# HIP4082driver.net
KiCad netlist of a schematic drawn in Altium Designer
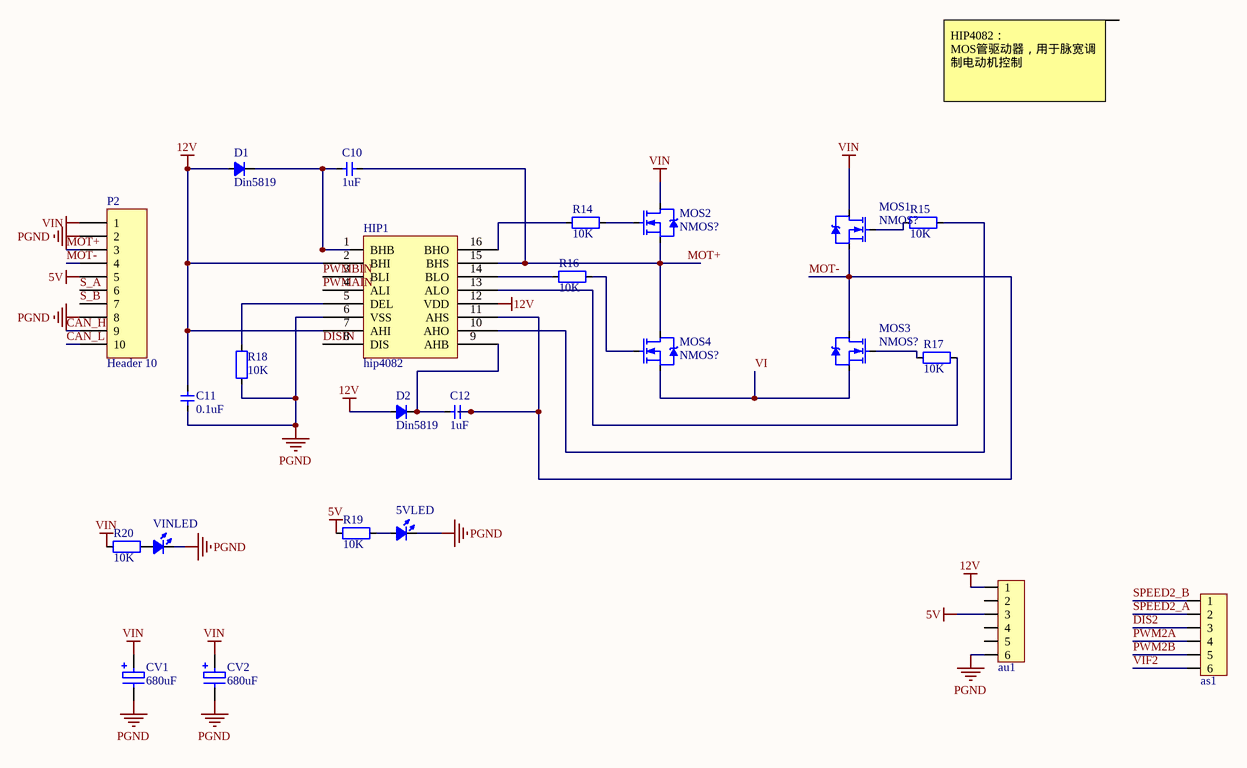
[diagram p0: HIP4082driver.SchDoc]

(export (version "E")
  (design (tool "Eeschema 10.0.6"))
  (components
    (comp (ref "5VLED")
      (value "LED_0805")
      (footprint "LED_0805_BLUE")
      (description "LED")
      (libsource (lib "SCH_Active") (part "LED_0603"))
    )
    (comp (ref "as1")
      (value "HDR1x6_2.54")
      (footprint "HDR1X6_2.54_180")
      (description "Header")
      (libsource (lib "Integrated_Library") (part "HDR1x6_2.54"))
    )
    (comp (ref "au1")
      (value "HDR1x6_2.54")
      (footprint "HDR1X6_2.54_180")
      (description "Header")
      (libsource (lib "Integrated_Library") (part "HDR1x6_2.54"))
    )
    (comp (ref "C10")
      (value "1uF")
      (footprint "CAP_0603")
      (description "Capacitor")
      (fields (field (name "Comment") "Cap_0603"))
      (libsource (lib "Integrated_Library") (part "Cap_0603"))
    )
    (comp (ref "C11")
      (value "0.1uF")
      (footprint "CAP_0603")
      (description "Capacitor")
      (fields (field (name "Comment") "Cap_0603"))
      (libsource (lib "Integrated_Library") (part "Cap_0603"))
    )
    (comp (ref "C12")
      (value "1uF")
      (footprint "CAP_0603")
      (description "Capacitor")
      (fields (field (name "Comment") "Cap_0603"))
      (libsource (lib "Integrated_Library") (part "Cap_0603"))
    )
    (comp (ref "CV1")
      (value "680uF")
      (footprint "CAP_ELE_680UF0.7X5MM")
      (description "电解电容")
      (fields (field (name "PUBLISHER") "Altium Limited"))
      (libsource (lib "Libraries_2014_0618") (part "CAP-ELE"))
    )
    (comp (ref "CV2")
      (value "680uF")
      (footprint "CAP_ELE_680UF0.7X5MM")
      (description "电解电容")
      (fields (field (name "PUBLISHER") "Altium Limited"))
      (libsource (lib "Libraries_2014_0618") (part "CAP-ELE"))
    )
    (comp (ref "D1")
      (value "Din5819")
      (footprint "SOD-323")
      (description "Diode")
      (libsource (lib "Integrated_Library") (part "Diode"))
    )
    (comp (ref "D2")
      (value "Din5819")
      (footprint "SOD-323")
      (description "Diode")
      (libsource (lib "Integrated_Library") (part "Diode"))
    )
    (comp (ref "HIP1") (value "hip4082") (footprint "SOP_E150_16") (libsource (lib "元件库") (part "hip4082")))
    (comp (ref "MOS1")
      (value "NMOS?")
      (footprint "PCB_IntegratedCircuit:TO-252AA")
      (description "MOSFET")
      (fields (field (name "Comment") "MOSFET_N"))
      (libsource (lib "SCH_Active") (part "MOSFET_N"))
    )
    (comp (ref "MOS2")
      (value "NMOS?")
      (footprint "PCB_IntegratedCircuit:TO-252AA")
      (description "MOSFET")
      (fields (field (name "Comment") "MOSFET_N"))
      (libsource (lib "SCH_Active") (part "MOSFET_N"))
    )
    (comp (ref "MOS3")
      (value "NMOS?")
      (footprint "PCB_IntegratedCircuit:TO-252AA")
      (description "MOSFET")
      (fields (field (name "Comment") "MOSFET_N"))
      (libsource (lib "SCH_Active") (part "MOSFET_N"))
    )
    (comp (ref "MOS4")
      (value "NMOS?")
      (footprint "PCB_IntegratedCircuit:TO-252AA")
      (description "MOSFET")
      (fields (field (name "Comment") "MOSFET_N"))
      (libsource (lib "SCH_Active") (part "MOSFET_N"))
    )
    (comp (ref "P2")
      (value "Header 10")
      (footprint "Green_10P")
      (description "Header, 10-Pin")
      (fields (field (name "PUBLISHER") "Altium Limited"))
      (libsource (lib "Libraries_2014_0618") (part "Header 10"))
    )
    (comp (ref "R14")
      (value "10K")
      (footprint "RES_0603")
      (description "Resistor")
      (fields (field (name "Comment") "Res_0603"))
      (libsource (lib "") (part "Res_0603_1"))
    )
    (comp (ref "R15")
      (value "10K")
      (footprint "RES_0603")
      (description "Resistor")
      (fields (field (name "Comment") "Res_0603"))
      (libsource (lib "") (part "Res_0603_1"))
    )
    (comp (ref "R16")
      (value "10K")
      (footprint "RES_0603")
      (description "Resistor")
      (fields (field (name "Comment") "Res_0603"))
      (libsource (lib "") (part "Res_0603_1"))
    )
    (comp (ref "R17")
      (value "10K")
      (footprint "RES_0603")
      (description "Resistor")
      (fields (field (name "Comment") "Res_0603"))
      (libsource (lib "") (part "Res_0603_1"))
    )
    (comp (ref "R18")
      (value "10K")
      (footprint "RES_0603")
      (description "Resistor")
      (fields (field (name "Comment") "Res_0603"))
      (libsource (lib "Integrated_Library") (part "Res_0603"))
    )
    (comp (ref "R19")
      (value "10K")
      (footprint "RES_0603")
      (description "Resistor")
      (fields (field (name "Comment") "Res_0603"))
      (libsource (lib "") (part "Res_0603_1"))
    )
    (comp (ref "R20")
      (value "10K")
      (footprint "RES_0603")
      (description "Resistor")
      (fields (field (name "Comment") "Res_0603"))
      (libsource (lib "") (part "Res_0603_1"))
    )
    (comp (ref "VINLED")
      (value "LED_0805")
      (footprint "LED_0805_RED")
      (description "LED")
      (libsource (lib "SCH_Active") (part "LED_0603"))
    )
  )
  (nets
    (net (code "1") (name "/CAN_H") (class "Default")
      (node (ref "P2") (pin "9") (pinfunction "9_9") (pintype "passive"))
    )
    (net (code "2") (name "/CAN_L") (class "Default")
      (node (ref "P2") (pin "10") (pinfunction "10_10") (pintype "passive"))
    )
    (net (code "3") (name "/DIS2") (class "Default")
      (node (ref "as1") (pin "3") (pinfunction "3_3") (pintype "passive"))
    )
    (net (code "4") (name "/DISIN") (class "Default")
      (node (ref "HIP1") (pin "8") (pinfunction "DIS_8") (pintype "passive"))
    )
    (net (code "5") (name "/MOT+") (class "Default")
      (node (ref "C10") (pin "2") (pinfunction "2_2") (pintype "passive"))
      (node (ref "HIP1") (pin "15") (pinfunction "BHS_15") (pintype "passive"))
      (node (ref "MOS2") (pin "3") (pinfunction "S_3") (pintype "passive"))
      (node (ref "MOS4") (pin "4") (pinfunction "D_4") (pintype "passive"))
      (node (ref "P2") (pin "3") (pinfunction "3_3") (pintype "passive"))
    )
    (net (code "6") (name "/MOT-") (class "Default")
      (node (ref "C12") (pin "2") (pinfunction "2_2") (pintype "passive"))
      (node (ref "HIP1") (pin "11") (pinfunction "AHS_11") (pintype "passive"))
      (node (ref "MOS1") (pin "3") (pinfunction "S_3") (pintype "passive"))
      (node (ref "MOS3") (pin "4") (pinfunction "D_4") (pintype "passive"))
      (node (ref "P2") (pin "4") (pinfunction "4_4") (pintype "passive"))
    )
    (net (code "7") (name "/PWM2A") (class "Default")
      (node (ref "as1") (pin "4") (pinfunction "4_4") (pintype "passive"))
    )
    (net (code "8") (name "/PWM2B") (class "Default")
      (node (ref "as1") (pin "5") (pinfunction "5_5") (pintype "passive"))
    )
    (net (code "9") (name "/PWMAIN") (class "Default")
      (node (ref "HIP1") (pin "4") (pinfunction "ALI_4") (pintype "passive"))
    )
    (net (code "10") (name "/PWMBIN") (class "Default")
      (node (ref "HIP1") (pin "3") (pinfunction "BLI_3") (pintype "passive"))
    )
    (net (code "11") (name "/SPEED2_A") (class "Default")
      (node (ref "as1") (pin "2") (pinfunction "2_2") (pintype "passive"))
    )
    (net (code "12") (name "/SPEED2_B") (class "Default")
      (node (ref "as1") (pin "1") (pinfunction "1_1") (pintype "passive"))
    )
    (net (code "13") (name "/S_A") (class "Default")
      (node (ref "P2") (pin "6") (pinfunction "6_6") (pintype "passive"))
    )
    (net (code "14") (name "/S_B") (class "Default")
      (node (ref "P2") (pin "7") (pinfunction "7_7") (pintype "passive"))
    )
    (net (code "15") (name "/VI") (class "Default")
      (node (ref "MOS3") (pin "3") (pinfunction "S_3") (pintype "passive"))
      (node (ref "MOS4") (pin "3") (pinfunction "S_3") (pintype "passive"))
    )
    (net (code "16") (name "/VIF2") (class "Default")
      (node (ref "as1") (pin "6") (pinfunction "6_6") (pintype "passive"))
    )
    (net (code "17") (name "5V") (class "Default")
      (node (ref "P2") (pin "5") (pinfunction "5_5") (pintype "passive"))
      (node (ref "R19") (pin "1") (pinfunction "1_1") (pintype "passive"))
      (node (ref "au1") (pin "3") (pinfunction "3_3") (pintype "passive"))
    )
    (net (code "18") (name "12V") (class "Default")
      (node (ref "C11") (pin "2") (pinfunction "2_2") (pintype "passive"))
      (node (ref "D1") (pin "1") (pinfunction "A_1") (pintype "passive"))
      (node (ref "D2") (pin "1") (pinfunction "A_1") (pintype "passive"))
      (node (ref "HIP1") (pin "12") (pinfunction "VDD_12") (pintype "passive"))
      (node (ref "HIP1") (pin "2") (pinfunction "BHI_2") (pintype "passive"))
      (node (ref "HIP1") (pin "7") (pinfunction "AHI_7") (pintype "passive"))
      (node (ref "au1") (pin "1") (pinfunction "1_1") (pintype "passive"))
    )
    (net (code "19") (name "Net-(5VLED-A)") (class "Default")
      (node (ref "5VLED") (pin "1") (pinfunction "A_1") (pintype "passive"))
      (node (ref "R19") (pin "2") (pinfunction "2_2") (pintype "passive"))
    )
    (net (code "20") (name "Net-(D1-K)") (class "Default")
      (node (ref "C10") (pin "1") (pinfunction "1_1") (pintype "passive"))
      (node (ref "D1") (pin "2") (pinfunction "K_2") (pintype "passive"))
      (node (ref "HIP1") (pin "1") (pinfunction "BHB_1") (pintype "passive"))
    )
    (net (code "21") (name "Net-(D2-K)") (class "Default")
      (node (ref "C12") (pin "1") (pinfunction "1_1") (pintype "passive"))
      (node (ref "D2") (pin "2") (pinfunction "K_2") (pintype "passive"))
      (node (ref "HIP1") (pin "9") (pinfunction "AHB_9") (pintype "passive"))
    )
    (net (code "22") (name "Net-(HIP1-AHO)") (class "Default")
      (node (ref "HIP1") (pin "10") (pinfunction "AHO_10") (pintype "passive"))
      (node (ref "R15") (pin "2") (pinfunction "2_2") (pintype "passive"))
    )
    (net (code "23") (name "Net-(HIP1-ALO)") (class "Default")
      (node (ref "HIP1") (pin "13") (pinfunction "ALO_13") (pintype "passive"))
      (node (ref "R17") (pin "2") (pinfunction "2_2") (pintype "passive"))
    )
    (net (code "24") (name "Net-(HIP1-BHO)") (class "Default")
      (node (ref "HIP1") (pin "16") (pinfunction "BHO_16") (pintype "passive"))
      (node (ref "R14") (pin "1") (pinfunction "1_1") (pintype "passive"))
    )
    (net (code "25") (name "Net-(HIP1-BLO)") (class "Default")
      (node (ref "HIP1") (pin "14") (pinfunction "BLO_14") (pintype "passive"))
      (node (ref "R16") (pin "1") (pinfunction "1_1") (pintype "passive"))
    )
    (net (code "26") (name "Net-(HIP1-DEL)") (class "Default")
      (node (ref "HIP1") (pin "5") (pinfunction "DEL_5") (pintype "passive"))
      (node (ref "R18") (pin "2") (pinfunction "2_2") (pintype "passive"))
    )
    (net (code "27") (name "Net-(MOS1-G)") (class "Default")
      (node (ref "MOS1") (pin "1") (pinfunction "G_1") (pintype "passive"))
      (node (ref "R15") (pin "1") (pinfunction "1_1") (pintype "passive"))
    )
    (net (code "28") (name "Net-(MOS2-G)") (class "Default")
      (node (ref "MOS2") (pin "1") (pinfunction "G_1") (pintype "passive"))
      (node (ref "R14") (pin "2") (pinfunction "2_2") (pintype "passive"))
    )
    (net (code "29") (name "Net-(MOS3-G)") (class "Default")
      (node (ref "MOS3") (pin "1") (pinfunction "G_1") (pintype "passive"))
      (node (ref "R17") (pin "1") (pinfunction "1_1") (pintype "passive"))
    )
    (net (code "30") (name "Net-(MOS4-G)") (class "Default")
      (node (ref "MOS4") (pin "1") (pinfunction "G_1") (pintype "passive"))
      (node (ref "R16") (pin "2") (pinfunction "2_2") (pintype "passive"))
    )
    (net (code "31") (name "Net-(VINLED-A)") (class "Default")
      (node (ref "R20") (pin "2") (pinfunction "2_2") (pintype "passive"))
      (node (ref "VINLED") (pin "1") (pinfunction "A_1") (pintype "passive"))
    )
    (net (code "32") (name "PGND") (class "Default")
      (node (ref "5VLED") (pin "2") (pinfunction "K_2") (pintype "passive"))
      (node (ref "C11") (pin "1") (pinfunction "1_1") (pintype "passive"))
      (node (ref "CV1") (pin "2") (pinfunction "2_2") (pintype "passive"))
      (node (ref "CV2") (pin "2") (pinfunction "2_2") (pintype "passive"))
      (node (ref "HIP1") (pin "6") (pinfunction "VSS_6") (pintype "passive"))
      (node (ref "P2") (pin "2") (pinfunction "2_2") (pintype "passive"))
      (node (ref "P2") (pin "8") (pinfunction "8_8") (pintype "passive"))
      (node (ref "R18") (pin "1") (pinfunction "1_1") (pintype "passive"))
      (node (ref "VINLED") (pin "2") (pinfunction "K_2") (pintype "passive"))
      (node (ref "au1") (pin "6") (pinfunction "6_6") (pintype "passive"))
    )
    (net (code "33") (name "VIN") (class "Default")
      (node (ref "CV1") (pin "1") (pinfunction "1_1") (pintype "passive"))
      (node (ref "CV2") (pin "1") (pinfunction "1_1") (pintype "passive"))
      (node (ref "MOS1") (pin "4") (pinfunction "D_4") (pintype "passive"))
      (node (ref "MOS2") (pin "4") (pinfunction "D_4") (pintype "passive"))
      (node (ref "P2") (pin "1") (pinfunction "1_1") (pintype "passive"))
      (node (ref "R20") (pin "1") (pinfunction "1_1") (pintype "passive"))
    )
    (net (code "34") (name "unconnected-(au1-Pad2)") (class "Default")
      (node (ref "au1") (pin "2") (pinfunction "2_2") (pintype "passive"))
    )
    (net (code "35") (name "unconnected-(au1-Pad4)") (class "Default")
      (node (ref "au1") (pin "4") (pinfunction "4_4") (pintype "passive"))
    )
    (net (code "36") (name "unconnected-(au1-Pad5)") (class "Default")
      (node (ref "au1") (pin "5") (pinfunction "5_5") (pintype "passive"))
    )
  )
)
